# LTM8055_AddonBoard_v1_0.net
KiCad netlist of a schematic drawn in EAGLE
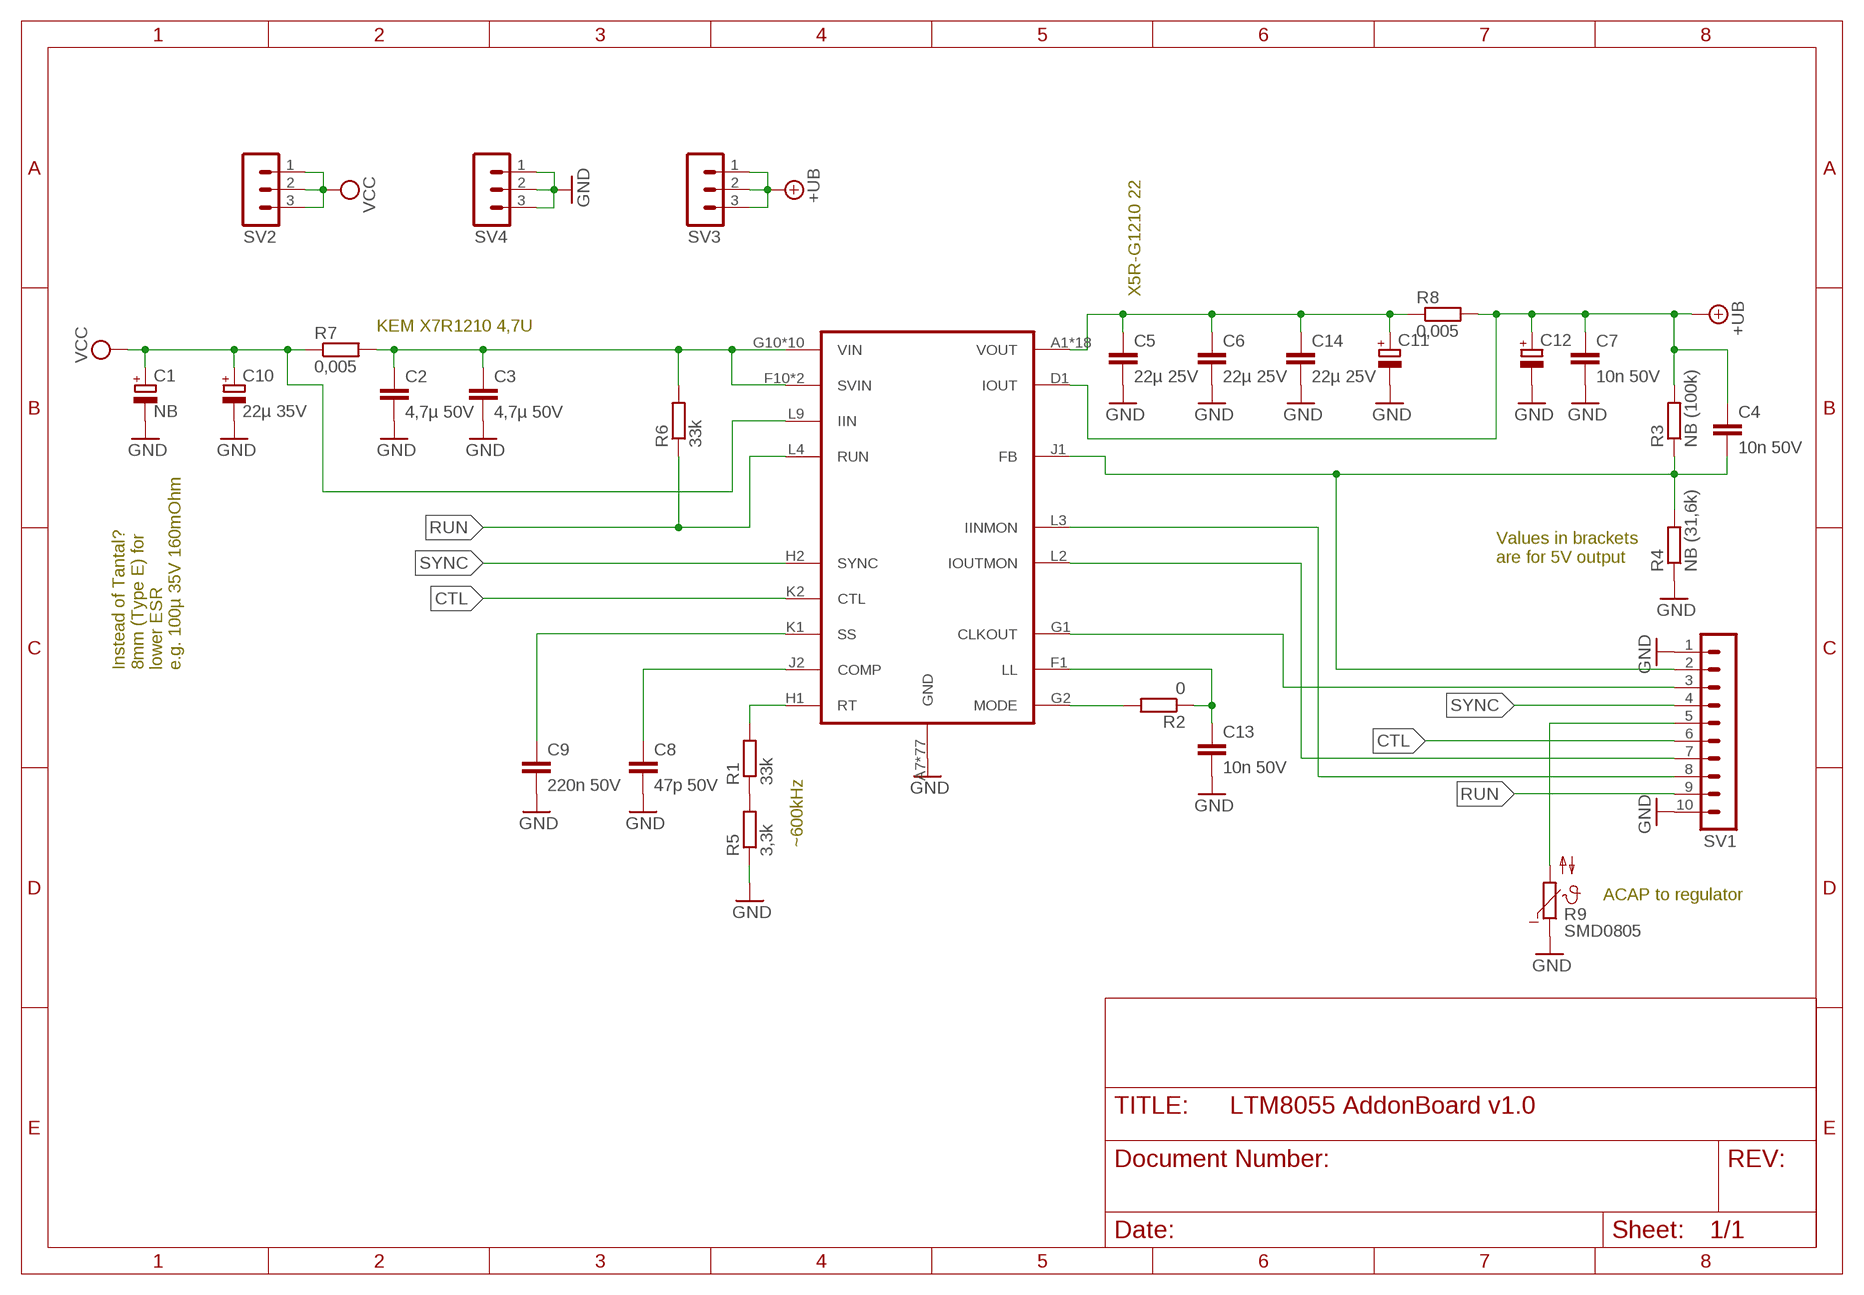
[diagram p0: schematic, sheet 1]

(export (version "E")
  (design (tool "Eeschema 10.0.6"))
  (components
    (comp (ref "C1")
      (value "NB")
      (footprint "eagle-import:PANASONIC_E")
      (libsource (lib "eagle-import") (part "CPOL-EUE"))
    )
    (comp (ref "C2")
      (value "4,7µ 50V")
      (footprint "eagle-import:C1206")
      (libsource (lib "eagle-import") (part "C-EUC1206"))
    )
    (comp (ref "C3")
      (value "4,7µ 50V")
      (footprint "eagle-import:C1206")
      (libsource (lib "eagle-import") (part "C-EUC1206"))
    )
    (comp (ref "C4")
      (value "10n 50V")
      (footprint "eagle-import:C0805")
      (libsource (lib "eagle-import") (part "C-EUC0805"))
    )
    (comp (ref "C5")
      (value "22µ 25V")
      (footprint "eagle-import:C1210")
      (libsource (lib "eagle-import") (part "C-EUC1210"))
    )
    (comp (ref "C6")
      (value "22µ 25V")
      (footprint "eagle-import:C1210")
      (libsource (lib "eagle-import") (part "C-EUC1210"))
    )
    (comp (ref "C7")
      (value "10n 50V")
      (footprint "eagle-import:C0805")
      (libsource (lib "eagle-import") (part "C-EUC0805"))
    )
    (comp (ref "C8")
      (value "47p 50V")
      (footprint "eagle-import:C0805")
      (libsource (lib "eagle-import") (part "C-EUC0805"))
    )
    (comp (ref "C9")
      (value "220n 50V")
      (footprint "eagle-import:C0805")
      (libsource (lib "eagle-import") (part "C-EUC0805"))
    )
    (comp (ref "C10")
      (value "22µ 35V")
      (footprint "eagle-import:D_7343-31R")
      (libsource (lib "eagle-import") (part "CPOL-EUD/7343-31R"))
    )
    (comp (ref "C11")
      (value "CPOL-EUD/7343-31R")
      (footprint "eagle-import:D_7343-31R")
      (libsource (lib "eagle-import") (part "CPOL-EUD/7343-31R"))
    )
    (comp (ref "C12")
      (value "CPOL-EUD/7343-31R")
      (footprint "eagle-import:D_7343-31R")
      (libsource (lib "eagle-import") (part "CPOL-EUD/7343-31R"))
    )
    (comp (ref "C13")
      (value "10n 50V")
      (footprint "eagle-import:C0805")
      (libsource (lib "eagle-import") (part "C-EUC0805"))
    )
    (comp (ref "C14")
      (value "22µ 25V")
      (footprint "eagle-import:C1210")
      (libsource (lib "eagle-import") (part "C-EUC1210"))
    )
    (comp (ref "IC1")
      (value "LTM8055-1")
      (footprint "eagle-import:BGA121_1.27_15X15MM")
      (libsource (lib "eagle-import") (part "LTM8055-1"))
    )
    (comp (ref "R1")
      (value "33k")
      (footprint "eagle-import:R0805")
      (libsource (lib "eagle-import") (part "R-EU_R0805"))
    )
    (comp (ref "R2")
      (value "0")
      (footprint "eagle-import:R0805")
      (libsource (lib "eagle-import") (part "R-EU_R0805"))
    )
    (comp (ref "R3")
      (value "NB (100k)")
      (footprint "eagle-import:R0805")
      (libsource (lib "eagle-import") (part "R-EU_R0805"))
    )
    (comp (ref "R4")
      (value "NB (31,6k)")
      (footprint "eagle-import:R0805")
      (libsource (lib "eagle-import") (part "R-EU_R0805"))
    )
    (comp (ref "R5")
      (value "3,3k")
      (footprint "eagle-import:R0805")
      (libsource (lib "eagle-import") (part "R-EU_R0805"))
    )
    (comp (ref "R6")
      (value "33k")
      (footprint "eagle-import:R0805")
      (libsource (lib "eagle-import") (part "R-EU_R0805"))
    )
    (comp (ref "R7")
      (value "0,005")
      (footprint "eagle-import:R2512")
      (libsource (lib "eagle-import") (part "R-EU_R2512"))
    )
    (comp (ref "R8")
      (value "0,005")
      (footprint "eagle-import:R2512")
      (libsource (lib "eagle-import") (part "R-EU_R2512"))
    )
    (comp (ref "R9")
      (value "SMD0805")
      (footprint "eagle-import:R0805")
      (libsource (lib "eagle-import") (part "SMD0805"))
    )
    (comp (ref "SV1")
      (value "MA10-1")
      (footprint "eagle-import:MA10-1")
      (libsource (lib "eagle-import") (part "MA10-1"))
    )
    (comp (ref "SV2")
      (value "MA03-1")
      (footprint "eagle-import:MA03-1")
      (libsource (lib "eagle-import") (part "MA03-1"))
    )
    (comp (ref "SV3")
      (value "MA03-1")
      (footprint "eagle-import:MA03-1")
      (libsource (lib "eagle-import") (part "MA03-1"))
    )
    (comp (ref "SV4")
      (value "MA03-1")
      (footprint "eagle-import:MA03-1")
      (libsource (lib "eagle-import") (part "MA03-1"))
    )
  )
  (nets
    (net (code "1") (name "+UB") (class "Default")
      (node (ref "C12") (pin "+") (pinfunction "+_+") (pintype "passive"))
      (node (ref "C4") (pin "1") (pinfunction "1_1") (pintype "passive"))
      (node (ref "C7") (pin "1") (pinfunction "1_1") (pintype "passive"))
      (node (ref "IC1") (pin "D1") (pinfunction "IOUT_D1") (pintype "bidirectional"))
      (node (ref "R3") (pin "2") (pinfunction "2_2") (pintype "passive"))
      (node (ref "R8") (pin "2") (pinfunction "2_2") (pintype "passive"))
      (node (ref "SV3") (pin "1") (pinfunction "1_1") (pintype "passive"))
      (node (ref "SV3") (pin "2") (pinfunction "2_2") (pintype "passive"))
      (node (ref "SV3") (pin "3") (pinfunction "3_3") (pintype "passive"))
    )
    (net (code "2") (name "CTL") (class "Default")
      (node (ref "IC1") (pin "K2") (pinfunction "CTL_K2") (pintype "bidirectional"))
      (node (ref "SV1") (pin "6") (pinfunction "6_6") (pintype "passive"))
    )
    (net (code "3") (name "GND") (class "Default")
      (node (ref "C1") (pin "-") (pinfunction "-_-") (pintype "passive"))
      (node (ref "C10") (pin "-") (pinfunction "-_-") (pintype "passive"))
      (node (ref "C11") (pin "-") (pinfunction "-_-") (pintype "passive"))
      (node (ref "C12") (pin "-") (pinfunction "-_-") (pintype "passive"))
      (node (ref "C13") (pin "2") (pinfunction "2_2") (pintype "passive"))
      (node (ref "C14") (pin "2") (pinfunction "2_2") (pintype "passive"))
      (node (ref "C2") (pin "2") (pinfunction "2_2") (pintype "passive"))
      (node (ref "C3") (pin "2") (pinfunction "2_2") (pintype "passive"))
      (node (ref "C5") (pin "2") (pinfunction "2_2") (pintype "passive"))
      (node (ref "C6") (pin "2") (pinfunction "2_2") (pintype "passive"))
      (node (ref "C7") (pin "2") (pinfunction "2_2") (pintype "passive"))
      (node (ref "C8") (pin "2") (pinfunction "2_2") (pintype "passive"))
      (node (ref "C9") (pin "2") (pinfunction "2_2") (pintype "passive"))
      (node (ref "IC1") (pin "A10") (pinfunction "GND_A10") (pintype "bidirectional"))
      (node (ref "IC1") (pin "A11") (pinfunction "GND_A11") (pintype "bidirectional"))
      (node (ref "IC1") (pin "A7") (pinfunction "GND_A7") (pintype "bidirectional"))
      (node (ref "IC1") (pin "A8") (pinfunction "GND_A8") (pintype "bidirectional"))
      (node (ref "IC1") (pin "A9") (pinfunction "GND_A9") (pintype "bidirectional"))
      (node (ref "IC1") (pin "B10") (pinfunction "GND_B10") (pintype "bidirectional"))
      (node (ref "IC1") (pin "B11") (pinfunction "GND_B11") (pintype "bidirectional"))
      (node (ref "IC1") (pin "B7") (pinfunction "GND_B7") (pintype "bidirectional"))
      (node (ref "IC1") (pin "B8") (pinfunction "GND_B8") (pintype "bidirectional"))
      (node (ref "IC1") (pin "B9") (pinfunction "GND_B9") (pintype "bidirectional"))
      (node (ref "IC1") (pin "C10") (pinfunction "GND_C10") (pintype "bidirectional"))
      (node (ref "IC1") (pin "C11") (pinfunction "GND_C11") (pintype "bidirectional"))
      (node (ref "IC1") (pin "C7") (pinfunction "GND_C7") (pintype "bidirectional"))
      (node (ref "IC1") (pin "C8") (pinfunction "GND_C8") (pintype "bidirectional"))
      (node (ref "IC1") (pin "C9") (pinfunction "GND_C9") (pintype "bidirectional"))
      (node (ref "IC1") (pin "D10") (pinfunction "GND_D10") (pintype "bidirectional"))
      (node (ref "IC1") (pin "D11") (pinfunction "GND_D11") (pintype "bidirectional"))
      (node (ref "IC1") (pin "D2") (pinfunction "GND_D2") (pintype "bidirectional"))
      (node (ref "IC1") (pin "D3") (pinfunction "GND_D3") (pintype "bidirectional"))
      (node (ref "IC1") (pin "D4") (pinfunction "GND_D4") (pintype "bidirectional"))
      (node (ref "IC1") (pin "D5") (pinfunction "GND_D5") (pintype "bidirectional"))
      (node (ref "IC1") (pin "D6") (pinfunction "GND_D6") (pintype "bidirectional"))
      (node (ref "IC1") (pin "D7") (pinfunction "GND_D7") (pintype "bidirectional"))
      (node (ref "IC1") (pin "D8") (pinfunction "GND_D8") (pintype "bidirectional"))
      (node (ref "IC1") (pin "D9") (pinfunction "GND_D9") (pintype "bidirectional"))
      (node (ref "IC1") (pin "E1") (pinfunction "GND_E1") (pintype "bidirectional"))
      (node (ref "IC1") (pin "E10") (pinfunction "GND_E10") (pintype "bidirectional"))
      (node (ref "IC1") (pin "E11") (pinfunction "GND_E11") (pintype "bidirectional"))
      (node (ref "IC1") (pin "E2") (pinfunction "GND_E2") (pintype "bidirectional"))
      (node (ref "IC1") (pin "E3") (pinfunction "GND_E3") (pintype "bidirectional"))
      (node (ref "IC1") (pin "E4") (pinfunction "GND_E4") (pintype "bidirectional"))
      (node (ref "IC1") (pin "E5") (pinfunction "GND_E5") (pintype "bidirectional"))
      (node (ref "IC1") (pin "E6") (pinfunction "GND_E6") (pintype "bidirectional"))
      (node (ref "IC1") (pin "E7") (pinfunction "GND_E7") (pintype "bidirectional"))
      (node (ref "IC1") (pin "E8") (pinfunction "GND_E8") (pintype "bidirectional"))
      (node (ref "IC1") (pin "E9") (pinfunction "GND_E9") (pintype "bidirectional"))
      (node (ref "IC1") (pin "F2") (pinfunction "GND_F2") (pintype "bidirectional"))
      (node (ref "IC1") (pin "F3") (pinfunction "GND_F3") (pintype "bidirectional"))
      (node (ref "IC1") (pin "F4") (pinfunction "GND_F4") (pintype "bidirectional"))
      (node (ref "IC1") (pin "F5") (pinfunction "GND_F5") (pintype "bidirectional"))
      (node (ref "IC1") (pin "F6") (pinfunction "GND_F6") (pintype "bidirectional"))
      (node (ref "IC1") (pin "F7") (pinfunction "GND_F7") (pintype "bidirectional"))
      (node (ref "IC1") (pin "F8") (pinfunction "GND_F8") (pintype "bidirectional"))
      (node (ref "IC1") (pin "F9") (pinfunction "GND_F9") (pintype "bidirectional"))
      (node (ref "IC1") (pin "G3") (pinfunction "GND_G3") (pintype "bidirectional"))
      (node (ref "IC1") (pin "G4") (pinfunction "GND_G4") (pintype "bidirectional"))
      (node (ref "IC1") (pin "G5") (pinfunction "GND_G5") (pintype "bidirectional"))
      (node (ref "IC1") (pin "G6") (pinfunction "GND_G6") (pintype "bidirectional"))
      (node (ref "IC1") (pin "G7") (pinfunction "GND_G7") (pintype "bidirectional"))
      (node (ref "IC1") (pin "G8") (pinfunction "GND_G8") (pintype "bidirectional"))
      (node (ref "IC1") (pin "G9") (pinfunction "GND_G9") (pintype "bidirectional"))
      (node (ref "IC1") (pin "H3") (pinfunction "GND_H3") (pintype "bidirectional"))
      (node (ref "IC1") (pin "H4") (pinfunction "GND_H4") (pintype "bidirectional"))
      (node (ref "IC1") (pin "H5") (pinfunction "GND_H5") (pintype "bidirectional"))
      (node (ref "IC1") (pin "H6") (pinfunction "GND_H6") (pintype "bidirectional"))
      (node (ref "IC1") (pin "H7") (pinfunction "GND_H7") (pintype "bidirectional"))
      (node (ref "IC1") (pin "H8") (pinfunction "GND_H8") (pintype "bidirectional"))
      (node (ref "IC1") (pin "H9") (pinfunction "GND_H9") (pintype "bidirectional"))
      (node (ref "IC1") (pin "J3") (pinfunction "GND_J3") (pintype "bidirectional"))
      (node (ref "IC1") (pin "J4") (pinfunction "GND_J4") (pintype "bidirectional"))
      (node (ref "IC1") (pin "J5") (pinfunction "GND_J5") (pintype "bidirectional"))
      (node (ref "IC1") (pin "J6") (pinfunction "GND_J6") (pintype "bidirectional"))
      (node (ref "IC1") (pin "J7") (pinfunction "GND_J7") (pintype "bidirectional"))
      (node (ref "IC1") (pin "J8") (pinfunction "GND_J8") (pintype "bidirectional"))
      (node (ref "IC1") (pin "J9") (pinfunction "GND_J9") (pintype "bidirectional"))
      (node (ref "IC1") (pin "K3") (pinfunction "GND_K3") (pintype "bidirectional"))
      (node (ref "IC1") (pin "K4") (pinfunction "GND_K4") (pintype "bidirectional"))
      (node (ref "IC1") (pin "K5") (pinfunction "GND_K5") (pintype "bidirectional"))
      (node (ref "IC1") (pin "K6") (pinfunction "GND_K6") (pintype "bidirectional"))
      (node (ref "IC1") (pin "K7") (pinfunction "GND_K7") (pintype "bidirectional"))
      (node (ref "IC1") (pin "K8") (pinfunction "GND_K8") (pintype "bidirectional"))
      (node (ref "IC1") (pin "K9") (pinfunction "GND_K9") (pintype "bidirectional"))
      (node (ref "IC1") (pin "L1") (pinfunction "GND_L1") (pintype "bidirectional"))
      (node (ref "IC1") (pin "L5") (pinfunction "GND_L5") (pintype "bidirectional"))
      (node (ref "IC1") (pin "L6") (pinfunction "GND_L6") (pintype "bidirectional"))
      (node (ref "IC1") (pin "L7") (pinfunction "GND_L7") (pintype "bidirectional"))
      (node (ref "IC1") (pin "L8") (pinfunction "GND_L8") (pintype "bidirectional"))
      (node (ref "R4") (pin "1") (pinfunction "1_1") (pintype "passive"))
      (node (ref "R5") (pin "1") (pinfunction "1_1") (pintype "passive"))
      (node (ref "R9") (pin "1") (pinfunction "1_1") (pintype "passive"))
      (node (ref "SV1") (pin "1") (pinfunction "1_1") (pintype "passive"))
      (node (ref "SV1") (pin "10") (pinfunction "10_10") (pintype "passive"))
      (node (ref "SV4") (pin "1") (pinfunction "1_1") (pintype "passive"))
      (node (ref "SV4") (pin "2") (pinfunction "2_2") (pintype "passive"))
      (node (ref "SV4") (pin "3") (pinfunction "3_3") (pintype "passive"))
    )
    (net (code "4") (name "Net-(C2-Pad1)") (class "Default")
      (node (ref "C2") (pin "1") (pinfunction "1_1") (pintype "passive"))
      (node (ref "C3") (pin "1") (pinfunction "1_1") (pintype "passive"))
      (node (ref "IC1") (pin "F10") (pinfunction "SVIN_F10") (pintype "bidirectional"))
      (node (ref "IC1") (pin "F11") (pinfunction "SVIN_F11") (pintype "bidirectional"))
      (node (ref "IC1") (pin "G10") (pinfunction "VIN_G10") (pintype "bidirectional"))
      (node (ref "IC1") (pin "G11") (pinfunction "VIN_G11") (pintype "bidirectional"))
      (node (ref "IC1") (pin "H10") (pinfunction "VIN_H10") (pintype "bidirectional"))
      (node (ref "IC1") (pin "H11") (pinfunction "VIN_H11") (pintype "bidirectional"))
      (node (ref "IC1") (pin "J10") (pinfunction "VIN_J10") (pintype "bidirectional"))
      (node (ref "IC1") (pin "J11") (pinfunction "VIN_J11") (pintype "bidirectional"))
      (node (ref "IC1") (pin "K10") (pinfunction "VIN_K10") (pintype "bidirectional"))
      (node (ref "IC1") (pin "K11") (pinfunction "VIN_K11") (pintype "bidirectional"))
      (node (ref "IC1") (pin "L10") (pinfunction "VIN_L10") (pintype "bidirectional"))
      (node (ref "IC1") (pin "L11") (pinfunction "VIN_L11") (pintype "bidirectional"))
      (node (ref "R6") (pin "2") (pinfunction "2_2") (pintype "passive"))
      (node (ref "R7") (pin "2") (pinfunction "2_2") (pintype "passive"))
    )
    (net (code "5") (name "Net-(C11-Pad+)") (class "Default")
      (node (ref "C11") (pin "+") (pinfunction "+_+") (pintype "passive"))
      (node (ref "C14") (pin "1") (pinfunction "1_1") (pintype "passive"))
      (node (ref "C5") (pin "1") (pinfunction "1_1") (pintype "passive"))
      (node (ref "C6") (pin "1") (pinfunction "1_1") (pintype "passive"))
      (node (ref "IC1") (pin "A1") (pinfunction "VOUT_A1") (pintype "bidirectional"))
      (node (ref "IC1") (pin "A2") (pinfunction "VOUT_A2") (pintype "bidirectional"))
      (node (ref "IC1") (pin "A3") (pinfunction "VOUT_A3") (pintype "bidirectional"))
      (node (ref "IC1") (pin "A4") (pinfunction "VOUT_A4") (pintype "bidirectional"))
      (node (ref "IC1") (pin "A5") (pinfunction "VOUT_A5") (pintype "bidirectional"))
      (node (ref "IC1") (pin "A6") (pinfunction "VOUT_A6") (pintype "bidirectional"))
      (node (ref "IC1") (pin "B1") (pinfunction "VOUT_B1") (pintype "bidirectional"))
      (node (ref "IC1") (pin "B2") (pinfunction "VOUT_B2") (pintype "bidirectional"))
      (node (ref "IC1") (pin "B3") (pinfunction "VOUT_B3") (pintype "bidirectional"))
      (node (ref "IC1") (pin "B4") (pinfunction "VOUT_B4") (pintype "bidirectional"))
      (node (ref "IC1") (pin "B5") (pinfunction "VOUT_B5") (pintype "bidirectional"))
      (node (ref "IC1") (pin "B6") (pinfunction "VOUT_B6") (pintype "bidirectional"))
      (node (ref "IC1") (pin "C1") (pinfunction "VOUT_C1") (pintype "bidirectional"))
      (node (ref "IC1") (pin "C2") (pinfunction "VOUT_C2") (pintype "bidirectional"))
      (node (ref "IC1") (pin "C3") (pinfunction "VOUT_C3") (pintype "bidirectional"))
      (node (ref "IC1") (pin "C4") (pinfunction "VOUT_C4") (pintype "bidirectional"))
      (node (ref "IC1") (pin "C5") (pinfunction "VOUT_C5") (pintype "bidirectional"))
      (node (ref "IC1") (pin "C6") (pinfunction "VOUT_C6") (pintype "bidirectional"))
      (node (ref "R8") (pin "1") (pinfunction "1_1") (pintype "passive"))
    )
    (net (code "6") (name "Net-(IC1-CLKOUT)") (class "Default")
      (node (ref "IC1") (pin "G1") (pinfunction "CLKOUT_G1") (pintype "bidirectional"))
      (node (ref "SV1") (pin "3") (pinfunction "3_3") (pintype "passive"))
    )
    (net (code "7") (name "Net-(IC1-COMP)") (class "Default")
      (node (ref "C8") (pin "1") (pinfunction "1_1") (pintype "passive"))
      (node (ref "IC1") (pin "J2") (pinfunction "COMP_J2") (pintype "bidirectional"))
    )
    (net (code "8") (name "Net-(IC1-FB)") (class "Default")
      (node (ref "C4") (pin "2") (pinfunction "2_2") (pintype "passive"))
      (node (ref "IC1") (pin "J1") (pinfunction "FB_J1") (pintype "bidirectional"))
      (node (ref "R3") (pin "1") (pinfunction "1_1") (pintype "passive"))
      (node (ref "R4") (pin "2") (pinfunction "2_2") (pintype "passive"))
      (node (ref "SV1") (pin "2") (pinfunction "2_2") (pintype "passive"))
    )
    (net (code "9") (name "Net-(IC1-IINMON)") (class "Default")
      (node (ref "IC1") (pin "L3") (pinfunction "IINMON_L3") (pintype "bidirectional"))
      (node (ref "SV1") (pin "8") (pinfunction "8_8") (pintype "passive"))
    )
    (net (code "10") (name "Net-(IC1-IOUTMON)") (class "Default")
      (node (ref "IC1") (pin "L2") (pinfunction "IOUTMON_L2") (pintype "bidirectional"))
      (node (ref "SV1") (pin "7") (pinfunction "7_7") (pintype "passive"))
    )
    (net (code "11") (name "Net-(IC1-LL)") (class "Default")
      (node (ref "C13") (pin "1") (pinfunction "1_1") (pintype "passive"))
      (node (ref "IC1") (pin "F1") (pinfunction "LL_F1") (pintype "bidirectional"))
      (node (ref "R2") (pin "1") (pinfunction "1_1") (pintype "passive"))
    )
    (net (code "12") (name "Net-(IC1-MODE)") (class "Default")
      (node (ref "IC1") (pin "G2") (pinfunction "MODE_G2") (pintype "bidirectional"))
      (node (ref "R2") (pin "2") (pinfunction "2_2") (pintype "passive"))
    )
    (net (code "13") (name "Net-(IC1-RT)") (class "Default")
      (node (ref "IC1") (pin "H1") (pinfunction "RT_H1") (pintype "bidirectional"))
      (node (ref "R1") (pin "2") (pinfunction "2_2") (pintype "passive"))
    )
    (net (code "14") (name "Net-(IC1-SS)") (class "Default")
      (node (ref "C9") (pin "1") (pinfunction "1_1") (pintype "passive"))
      (node (ref "IC1") (pin "K1") (pinfunction "SS_K1") (pintype "bidirectional"))
    )
    (net (code "15") (name "Net-(R1-Pad1)") (class "Default")
      (node (ref "R1") (pin "1") (pinfunction "1_1") (pintype "passive"))
      (node (ref "R5") (pin "2") (pinfunction "2_2") (pintype "passive"))
    )
    (net (code "16") (name "Net-(R9-Pad2)") (class "Default")
      (node (ref "R9") (pin "2") (pinfunction "2_2") (pintype "passive"))
      (node (ref "SV1") (pin "5") (pinfunction "5_5") (pintype "passive"))
    )
    (net (code "17") (name "RUN") (class "Default")
      (node (ref "IC1") (pin "L4") (pinfunction "RUN_L4") (pintype "bidirectional"))
      (node (ref "R6") (pin "1") (pinfunction "1_1") (pintype "passive"))
      (node (ref "SV1") (pin "9") (pinfunction "9_9") (pintype "passive"))
    )
    (net (code "18") (name "SYNC") (class "Default")
      (node (ref "IC1") (pin "H2") (pinfunction "SYNC_H2") (pintype "bidirectional"))
      (node (ref "SV1") (pin "4") (pinfunction "4_4") (pintype "passive"))
    )
    (net (code "19") (name "VCC") (class "Default")
      (node (ref "C1") (pin "+") (pinfunction "+_+") (pintype "passive"))
      (node (ref "C10") (pin "+") (pinfunction "+_+") (pintype "passive"))
      (node (ref "IC1") (pin "L9") (pinfunction "IIN_L9") (pintype "bidirectional"))
      (node (ref "R7") (pin "1") (pinfunction "1_1") (pintype "passive"))
      (node (ref "SV2") (pin "1") (pinfunction "1_1") (pintype "passive"))
      (node (ref "SV2") (pin "2") (pinfunction "2_2") (pintype "passive"))
      (node (ref "SV2") (pin "3") (pinfunction "3_3") (pintype "passive"))
    )
  )
)
